# digital_logic.net
KiCad netlist of a schematic drawn in Altium Designer
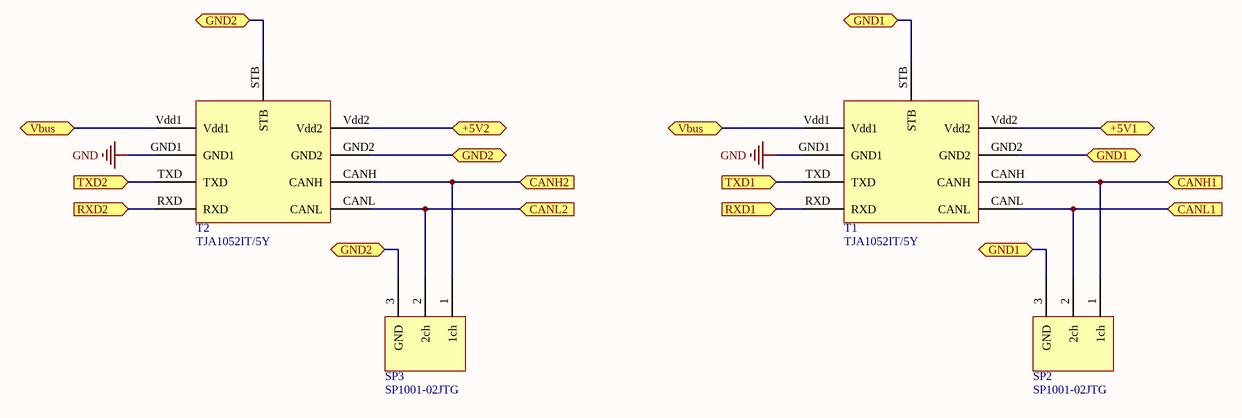
[diagram p0: digital logic.SchDoc]

(export (version "E")
  (design (tool "Eeschema 10.0.6"))
  (components
    (comp (ref "SP2")
      (value "SP1001-02JTG")
      (footprint "SC70-3")
      (libsource (lib "lib") (part "SP1001-02JTG"))
    )
    (comp (ref "SP3")
      (value "SP1001-02JTG")
      (footprint "SC70-3")
      (libsource (lib "lib") (part "SP1001-02JTG"))
    )
    (comp (ref "T1")
      (value "TJA1052IT/5Y")
      (footprint "TJA1052")
      (libsource (lib "lib") (part "TJA1052IT/5Y"))
    )
    (comp (ref "T2")
      (value "TJA1052IT/5Y")
      (footprint "TJA1052")
      (libsource (lib "lib") (part "TJA1052IT/5Y"))
    )
  )
  (nets
    (net (code "1") (name "/+5V1") (class "Default")
      (node (ref "T1") (pin "Vdd2") (pinfunction "Vdd2_Vdd2") (pintype "passive"))
    )
    (net (code "2") (name "/+5V2") (class "Default")
      (node (ref "T2") (pin "Vdd2") (pinfunction "Vdd2_Vdd2") (pintype "passive"))
    )
    (net (code "3") (name "/CANH1") (class "Default")
      (node (ref "SP2") (pin "1") (pinfunction "1ch_1") (pintype "passive"))
      (node (ref "T1") (pin "CANH") (pinfunction "CANH_CANH") (pintype "passive"))
    )
    (net (code "4") (name "/CANH2") (class "Default")
      (node (ref "SP3") (pin "1") (pinfunction "1ch_1") (pintype "passive"))
      (node (ref "T2") (pin "CANH") (pinfunction "CANH_CANH") (pintype "passive"))
    )
    (net (code "5") (name "/CANL1") (class "Default")
      (node (ref "SP2") (pin "2") (pinfunction "2ch_2") (pintype "passive"))
      (node (ref "T1") (pin "CANL") (pinfunction "CANL_CANL") (pintype "passive"))
    )
    (net (code "6") (name "/CANL2") (class "Default")
      (node (ref "SP3") (pin "2") (pinfunction "2ch_2") (pintype "passive"))
      (node (ref "T2") (pin "CANL") (pinfunction "CANL_CANL") (pintype "passive"))
    )
    (net (code "7") (name "/GND1") (class "Default")
      (node (ref "SP2") (pin "3") (pinfunction "GND_3") (pintype "passive"))
      (node (ref "T1") (pin "GND2") (pinfunction "GND2_GND2") (pintype "passive"))
      (node (ref "T1") (pin "STB") (pinfunction "STB_STB") (pintype "passive"))
    )
    (net (code "8") (name "/GND2") (class "Default")
      (node (ref "SP3") (pin "3") (pinfunction "GND_3") (pintype "passive"))
      (node (ref "T2") (pin "GND2") (pinfunction "GND2_GND2") (pintype "passive"))
      (node (ref "T2") (pin "STB") (pinfunction "STB_STB") (pintype "passive"))
    )
    (net (code "9") (name "/RXD1") (class "Default")
      (node (ref "T1") (pin "RXD") (pinfunction "RXD_RXD") (pintype "passive"))
    )
    (net (code "10") (name "/RXD2") (class "Default")
      (node (ref "T2") (pin "RXD") (pinfunction "RXD_RXD") (pintype "passive"))
    )
    (net (code "11") (name "/TXD1") (class "Default")
      (node (ref "T1") (pin "TXD") (pinfunction "TXD_TXD") (pintype "passive"))
    )
    (net (code "12") (name "/TXD2") (class "Default")
      (node (ref "T2") (pin "TXD") (pinfunction "TXD_TXD") (pintype "passive"))
    )
    (net (code "13") (name "/Vbus") (class "Default")
      (node (ref "T1") (pin "Vdd1") (pinfunction "Vdd1_Vdd1") (pintype "passive"))
      (node (ref "T2") (pin "Vdd1") (pinfunction "Vdd1_Vdd1") (pintype "passive"))
    )
    (net (code "14") (name "GND") (class "Default")
      (node (ref "T1") (pin "GND1") (pinfunction "GND1_GND1") (pintype "passive"))
      (node (ref "T2") (pin "GND1") (pinfunction "GND1_GND1") (pintype "passive"))
    )
  )
)
